# ATTINY214-SSNR.net
KiCad netlist of a schematic drawn in Altium Designer
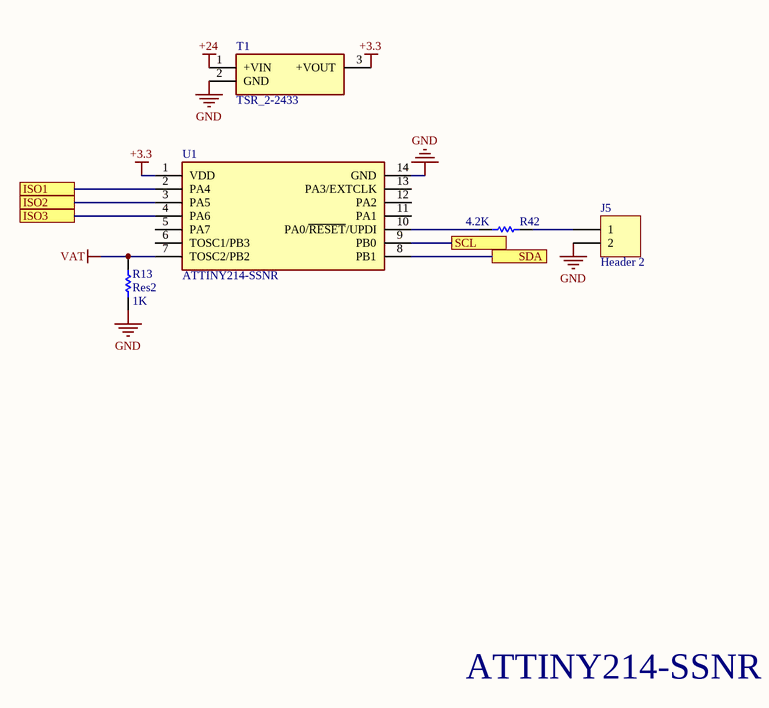
[diagram p0: ATTINY214-SSNR.SchDoc]

(export (version "E")
  (design (tool "Eeschema 10.0.6"))
  (components
    (comp (ref "J5")
      (value "Header 2")
      (footprint "HDR1X2")
      (description "Header, 2-Pin")
      (fields (field (name "PUBLISHER") "Altium Limited"))
      (libsource (lib "Miscellaneous Connectors") (part "Header 2"))
    )
    (comp (ref "R13")
      (value "Res2")
      (footprint "0402")
      (description "Resistor")
      (fields (field (name "ALTIUM_VALUE") "1K") (field (name "PUBLISHER") "Altium Limited"))
      (libsource (lib "Miscellaneous Devices") (part "Res1"))
    )
    (comp (ref "R42")
      (value "4.2K")
      (footprint "0402")
      (description "Resistor")
      (fields (field (name "Comment") "Res10") (field (name "PUBLISHER") "Altium Limited"))
      (libsource (lib "Miscellaneous Devices") (part "Res1"))
    )
    (comp (ref "T1")
      (value "TSR_2-2433")
      (footprint "TSR_2-2433")
      (description "Transformer")
      (fields
        (field (name "MANUFACTURER_PART_NUMBER") "TSR 2-2433")
        (field (name "MOUSER PART NUMBER") "495-TSR2-2433")
      )
      (libsource (lib "*") (part "TSR_2-2433"))
    )
    (comp (ref "U1")
      (value "ATTINY214-SSNR")
      (footprint "SOIC127P600X175-14N")
      (description "Undefined or Miscellaneous")
      (fields (field (name "MOUSER PART NUMBER") "579-ATTINY214-SSNR"))
      (libsource (lib "*") (part "ATTINY214-SSNR"))
    )
  )
  (nets
    (net (code "1") (name "+3.3") (class "Default")
      (node (ref "T1") (pin "3") (pinfunction "+VOUT_3") (pintype "passive"))
      (node (ref "U1") (pin "1") (pinfunction "VDD_1") (pintype "passive"))
    )
    (net (code "2") (name "+24") (class "Default")
      (node (ref "T1") (pin "1") (pinfunction "+VIN_1") (pintype "passive"))
    )
    (net (code "3") (name "/ISO1") (class "Default")
      (node (ref "U1") (pin "2") (pinfunction "PA4_2") (pintype "passive"))
    )
    (net (code "4") (name "/ISO2") (class "Default")
      (node (ref "U1") (pin "3") (pinfunction "PA5_3") (pintype "passive"))
    )
    (net (code "5") (name "/ISO3") (class "Default")
      (node (ref "U1") (pin "4") (pinfunction "PA6_4") (pintype "passive"))
    )
    (net (code "6") (name "/SCL") (class "Default")
      (node (ref "U1") (pin "9") (pinfunction "PB0_9") (pintype "passive"))
    )
    (net (code "7") (name "/SDA") (class "Default")
      (node (ref "U1") (pin "8") (pinfunction "PB1_8") (pintype "passive"))
    )
    (net (code "8") (name "GND") (class "Default")
      (node (ref "J5") (pin "2") (pinfunction "2_2") (pintype "passive"))
      (node (ref "R13") (pin "1") (pinfunction "1_1") (pintype "passive"))
      (node (ref "T1") (pin "2") (pinfunction "GND_2") (pintype "passive"))
      (node (ref "U1") (pin "14") (pinfunction "GND_14") (pintype "passive"))
    )
    (net (code "9") (name "Net-(J5-Pad1)") (class "Default")
      (node (ref "J5") (pin "1") (pinfunction "1_1") (pintype "passive"))
      (node (ref "R42") (pin "2") (pinfunction "2_2") (pintype "passive"))
    )
    (net (code "10") (name "Net-(U1-PA0{slash}~{RESET}{slash}UPDI)") (class "Default")
      (node (ref "R42") (pin "1") (pinfunction "1_1") (pintype "passive"))
      (node (ref "U1") (pin "10") (pinfunction "PA0/~{RESET}/UPDI_10") (pintype "passive"))
    )
    (net (code "11") (name "VAT") (class "Default")
      (node (ref "R13") (pin "2") (pinfunction "2_2") (pintype "passive"))
      (node (ref "U1") (pin "7") (pinfunction "TOSC2/PB2_7") (pintype "passive"))
    )
    (net (code "12") (name "unconnected-(U1-PA1-Pad11)") (class "Default")
      (node (ref "U1") (pin "11") (pinfunction "PA1_11") (pintype "passive"))
    )
    (net (code "13") (name "unconnected-(U1-PA2-Pad12)") (class "Default")
      (node (ref "U1") (pin "12") (pinfunction "PA2_12") (pintype "passive"))
    )
    (net (code "14") (name "unconnected-(U1-PA3{slash}EXTCLK-Pad13)") (class "Default")
      (node (ref "U1") (pin "13") (pinfunction "PA3/EXTCLK_13") (pintype "passive"))
    )
    (net (code "15") (name "unconnected-(U1-PA7-Pad5)") (class "Default")
      (node (ref "U1") (pin "5") (pinfunction "PA7_5") (pintype "passive"))
    )
    (net (code "16") (name "unconnected-(U1-TOSC1{slash}PB3-Pad6)") (class "Default")
      (node (ref "U1") (pin "6") (pinfunction "TOSC1/PB3_6") (pintype "passive"))
    )
  )
)
